# Back.net
KiCad netlist of a schematic drawn in Altium Designer
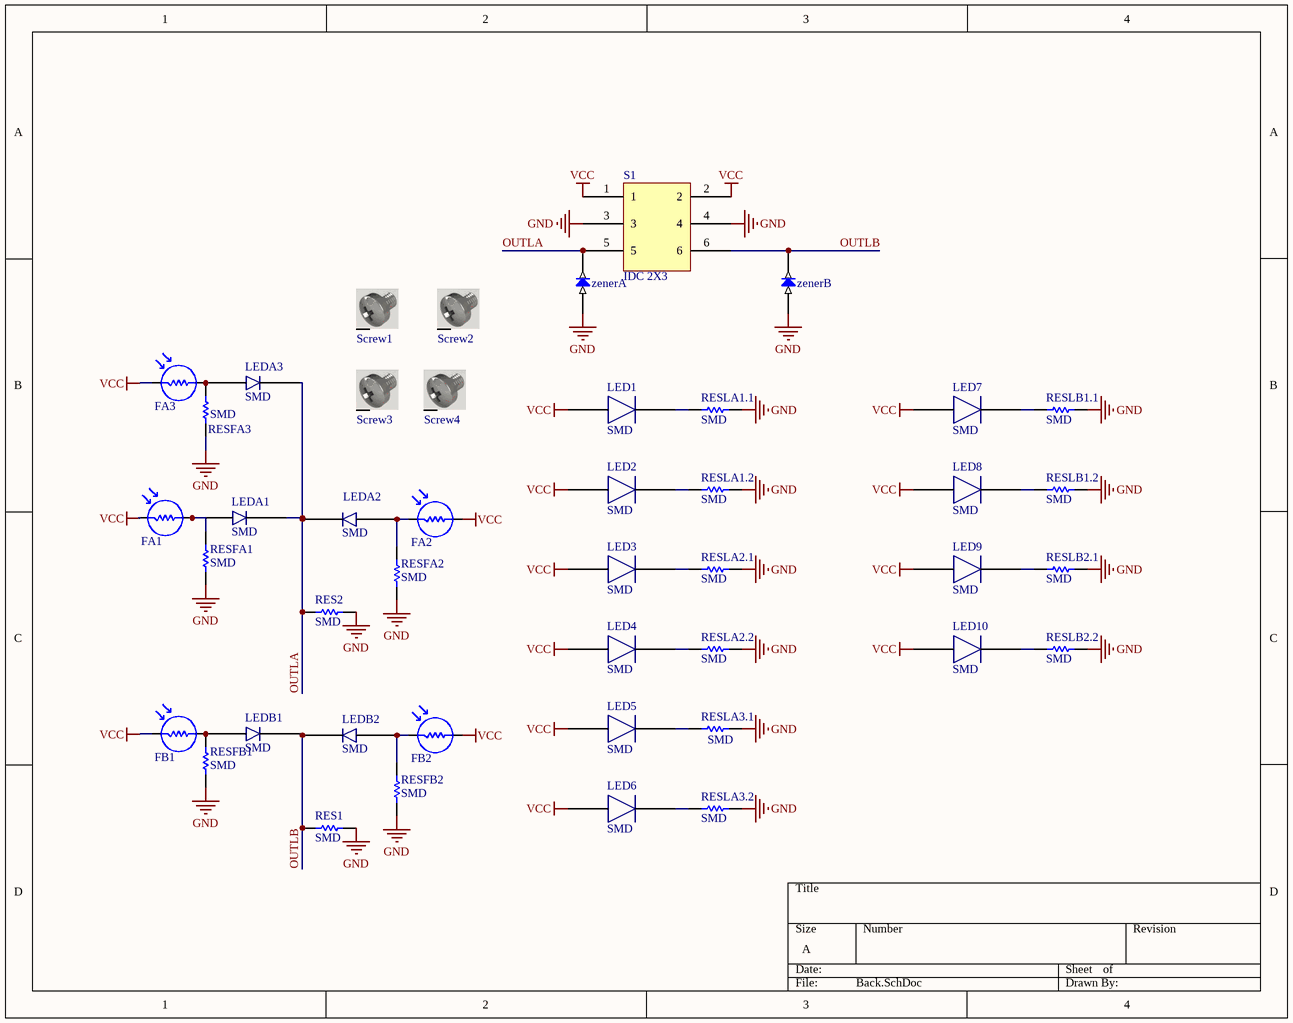
[diagram p0: Back.SchDoc]

(export (version "E")
  (design (tool "Eeschema 10.0.6"))
  (components
    (comp (ref "FA1")
      (value "Photo Cell")
      (footprint "PhotoCell.")
      (fields (field (name "PUBLISHER") "Altium Limited"))
      (libsource (lib "Farzanegan") (part "Photo Cell.."))
    )
    (comp (ref "FA2")
      (value "Photo Cell")
      (footprint "PhotoCell.")
      (fields (field (name "PUBLISHER") "Altium Limited"))
      (libsource (lib "Farzanegan") (part "Photo Cell.."))
    )
    (comp (ref "FA3")
      (value "Photo Cell")
      (footprint "PhotoCell.")
      (fields (field (name "PUBLISHER") "Altium Limited"))
      (libsource (lib "Farzanegan") (part "Photo Cell.."))
    )
    (comp (ref "FB1")
      (value "Photo Cell")
      (footprint "PhotoCell.")
      (fields (field (name "PUBLISHER") "Altium Limited"))
      (libsource (lib "Farzanegan") (part "Photo Cell.."))
    )
    (comp (ref "FB2")
      (value "Photo Cell")
      (footprint "PhotoCell.")
      (fields (field (name "PUBLISHER") "Altium Limited"))
      (libsource (lib "Farzanegan") (part "Photo Cell.."))
    )
    (comp (ref "LED1") (value "SMD") (footprint "LED SMD") (libsource (lib "Farzanegan") (part "LED SMD")))
    (comp (ref "LED2") (value "SMD") (footprint "LED SMD") (libsource (lib "Farzanegan") (part "LED SMD")))
    (comp (ref "LED3") (value "SMD") (footprint "LED SMD") (libsource (lib "Farzanegan") (part "LED SMD")))
    (comp (ref "LED4") (value "SMD") (footprint "LED SMD") (libsource (lib "Farzanegan") (part "LED SMD")))
    (comp (ref "LED5") (value "SMD") (footprint "LED SMD") (libsource (lib "Farzanegan") (part "LED SMD")))
    (comp (ref "LED6") (value "SMD") (footprint "LED SMD") (libsource (lib "Farzanegan") (part "LED SMD")))
    (comp (ref "LED7") (value "SMD") (footprint "LED SMD") (libsource (lib "Farzanegan") (part "LED SMD")))
    (comp (ref "LED8") (value "SMD") (footprint "LED SMD") (libsource (lib "Farzanegan") (part "LED SMD")))
    (comp (ref "LED9") (value "SMD") (footprint "LED SMD") (libsource (lib "Farzanegan") (part "LED SMD")))
    (comp (ref "LED10") (value "SMD") (footprint "LED SMD") (libsource (lib "Farzanegan") (part "LED SMD")))
    (comp (ref "LEDA1") (value "SMD") (footprint "LED SMD") (libsource (lib "") (part "LED SMD_1")))
    (comp (ref "LEDA2") (value "SMD") (footprint "LED SMD") (libsource (lib "") (part "LED SMD_1")))
    (comp (ref "LEDA3") (value "SMD") (footprint "LED SMD") (libsource (lib "") (part "LED SMD_1")))
    (comp (ref "LEDB1") (value "SMD") (footprint "LED SMD") (libsource (lib "") (part "LED SMD_1")))
    (comp (ref "LEDB2") (value "SMD") (footprint "LED SMD") (libsource (lib "") (part "LED SMD_1")))
    (comp (ref "RES1")
      (value "SMD")
      (footprint "Resistor SMD 1206")
      (libsource (lib "Farzanegan") (part "Res SMD"))
    )
    (comp (ref "RES2")
      (value "SMD")
      (footprint "Resistor SMD 1206")
      (libsource (lib "Farzanegan") (part "Res SMD"))
    )
    (comp (ref "RESFA1")
      (value "SMD")
      (footprint "Resistor SMD 1206")
      (libsource (lib "Farzanegan") (part "Res SMD"))
    )
    (comp (ref "RESFA2")
      (value "SMD")
      (footprint "Resistor SMD 1206")
      (libsource (lib "Farzanegan") (part "Res SMD"))
    )
    (comp (ref "RESFA3")
      (value "SMD")
      (footprint "Resistor SMD 1206")
      (libsource (lib "Farzanegan") (part "Res SMD"))
    )
    (comp (ref "RESFB1")
      (value "SMD")
      (footprint "Resistor SMD 1206")
      (libsource (lib "Farzanegan") (part "Res SMD"))
    )
    (comp (ref "RESFB2")
      (value "SMD")
      (footprint "Resistor SMD 1206")
      (libsource (lib "Farzanegan") (part "Res SMD"))
    )
    (comp (ref "RESLA1.1")
      (value "SMD")
      (footprint "Resistor SMD 1206")
      (libsource (lib "Farzanegan") (part "Res SMD"))
    )
    (comp (ref "RESLA1.2")
      (value "SMD")
      (footprint "Resistor SMD 1206")
      (libsource (lib "Farzanegan") (part "Res SMD"))
    )
    (comp (ref "RESLA2.1")
      (value "SMD")
      (footprint "Resistor SMD 1206")
      (libsource (lib "Farzanegan") (part "Res SMD"))
    )
    (comp (ref "RESLA2.2")
      (value "SMD")
      (footprint "Resistor SMD 1206")
      (libsource (lib "Farzanegan") (part "Res SMD"))
    )
    (comp (ref "RESLA3.1")
      (value "SMD")
      (footprint "Resistor SMD 1206")
      (libsource (lib "Farzanegan") (part "Res SMD"))
    )
    (comp (ref "RESLA3.2")
      (value "SMD")
      (footprint "Resistor SMD 1206")
      (libsource (lib "Farzanegan") (part "Res SMD"))
    )
    (comp (ref "RESLB1.1")
      (value "SMD")
      (footprint "Resistor SMD 1206")
      (libsource (lib "Farzanegan") (part "Res SMD"))
    )
    (comp (ref "RESLB1.2")
      (value "SMD")
      (footprint "Resistor SMD 1206")
      (libsource (lib "Farzanegan") (part "Res SMD"))
    )
    (comp (ref "RESLB2.1")
      (value "SMD")
      (footprint "Resistor SMD 1206")
      (libsource (lib "Farzanegan") (part "Res SMD"))
    )
    (comp (ref "RESLB2.2")
      (value "SMD")
      (footprint "Resistor SMD 1206")
      (libsource (lib "Farzanegan") (part "Res SMD"))
    )
    (comp (ref "S1") (value "IDC 2X3") (footprint "IDC 2X3") (libsource (lib "Farzanegan") (part "IDC 2X3")))
    (comp (ref "Screw1")
      (value "Screw")
      (footprint "Screw")
      (fields (field (name "PUBLISHER") "Altium Limited"))
      (libsource (lib "Farzanegan") (part "Screw"))
    )
    (comp (ref "Screw2")
      (value "Screw")
      (footprint "Screw")
      (fields (field (name "PUBLISHER") "Altium Limited"))
      (libsource (lib "Farzanegan") (part "Screw"))
    )
    (comp (ref "Screw3")
      (value "Screw")
      (footprint "Screw")
      (fields (field (name "PUBLISHER") "Altium Limited"))
      (libsource (lib "Farzanegan") (part "Screw"))
    )
    (comp (ref "Screw4")
      (value "Screw")
      (footprint "Screw")
      (fields (field (name "PUBLISHER") "Altium Limited"))
      (libsource (lib "Farzanegan") (part "Screw"))
    )
    (comp (ref "zenerA")
      (value "zener")
      (footprint "LED SMD")
      (libsource (lib "Farz1") (part "SMDZenerDiode"))
    )
    (comp (ref "zenerB")
      (value "zener")
      (footprint "LED SMD")
      (libsource (lib "Farz1") (part "SMDZenerDiode"))
    )
  )
  (nets
    (net (code "1") (name "/OUTLA") (class "Default")
      (node (ref "LEDA1") (pin "2") (pinfunction "2_2") (pintype "passive"))
      (node (ref "LEDA2") (pin "2") (pinfunction "2_2") (pintype "passive"))
      (node (ref "LEDA3") (pin "2") (pinfunction "2_2") (pintype "passive"))
      (node (ref "RES2") (pin "1") (pinfunction "1_1") (pintype "passive"))
      (node (ref "S1") (pin "5") (pinfunction "5_5") (pintype "passive"))
      (node (ref "zenerA") (pin "2") (pinfunction "out_2") (pintype "output"))
    )
    (net (code "2") (name "/OUTLB") (class "Default")
      (node (ref "LEDB1") (pin "2") (pinfunction "2_2") (pintype "passive"))
      (node (ref "LEDB2") (pin "2") (pinfunction "2_2") (pintype "passive"))
      (node (ref "RES1") (pin "1") (pinfunction "1_1") (pintype "passive"))
      (node (ref "S1") (pin "6") (pinfunction "6_6") (pintype "passive"))
      (node (ref "zenerB") (pin "2") (pinfunction "out_2") (pintype "output"))
    )
    (net (code "3") (name "GND") (class "Default")
      (node (ref "RES1") (pin "2") (pinfunction "2_2") (pintype "passive"))
      (node (ref "RES2") (pin "2") (pinfunction "2_2") (pintype "passive"))
      (node (ref "RESFA1") (pin "1") (pinfunction "1_1") (pintype "passive"))
      (node (ref "RESFA2") (pin "1") (pinfunction "1_1") (pintype "passive"))
      (node (ref "RESFA3") (pin "1") (pinfunction "1_1") (pintype "passive"))
      (node (ref "RESFB1") (pin "1") (pinfunction "1_1") (pintype "passive"))
      (node (ref "RESFB2") (pin "1") (pinfunction "1_1") (pintype "passive"))
      (node (ref "RESLA1.1") (pin "2") (pinfunction "2_2") (pintype "passive"))
      (node (ref "RESLA1.2") (pin "2") (pinfunction "2_2") (pintype "passive"))
      (node (ref "RESLA2.1") (pin "2") (pinfunction "2_2") (pintype "passive"))
      (node (ref "RESLA2.2") (pin "2") (pinfunction "2_2") (pintype "passive"))
      (node (ref "RESLA3.1") (pin "2") (pinfunction "2_2") (pintype "passive"))
      (node (ref "RESLA3.2") (pin "2") (pinfunction "2_2") (pintype "passive"))
      (node (ref "RESLB1.1") (pin "2") (pinfunction "2_2") (pintype "passive"))
      (node (ref "RESLB1.2") (pin "2") (pinfunction "2_2") (pintype "passive"))
      (node (ref "RESLB2.1") (pin "2") (pinfunction "2_2") (pintype "passive"))
      (node (ref "RESLB2.2") (pin "2") (pinfunction "2_2") (pintype "passive"))
      (node (ref "S1") (pin "3") (pinfunction "3_3") (pintype "passive"))
      (node (ref "S1") (pin "4") (pinfunction "4_4") (pintype "passive"))
      (node (ref "zenerA") (pin "1") (pinfunction "in_1") (pintype "input"))
      (node (ref "zenerB") (pin "1") (pinfunction "in_1") (pintype "input"))
    )
    (net (code "4") (name "Net-(FA1-Pad2)") (class "Default")
      (node (ref "FA1") (pin "2") (pintype "passive"))
      (node (ref "LEDA1") (pin "1") (pinfunction "1_1") (pintype "passive"))
      (node (ref "RESFA1") (pin "2") (pinfunction "2_2") (pintype "passive"))
    )
    (net (code "5") (name "Net-(FA2-Pad1)") (class "Default")
      (node (ref "FA2") (pin "1") (pintype "passive"))
      (node (ref "LEDA2") (pin "1") (pinfunction "1_1") (pintype "passive"))
      (node (ref "RESFA2") (pin "2") (pinfunction "2_2") (pintype "passive"))
    )
    (net (code "6") (name "Net-(FA3-Pad2)") (class "Default")
      (node (ref "FA3") (pin "2") (pintype "passive"))
      (node (ref "LEDA3") (pin "1") (pinfunction "1_1") (pintype "passive"))
      (node (ref "RESFA3") (pin "2") (pinfunction "2_2") (pintype "passive"))
    )
    (net (code "7") (name "Net-(FB1-Pad2)") (class "Default")
      (node (ref "FB1") (pin "2") (pintype "passive"))
      (node (ref "LEDB1") (pin "1") (pinfunction "1_1") (pintype "passive"))
      (node (ref "RESFB1") (pin "2") (pinfunction "2_2") (pintype "passive"))
    )
    (net (code "8") (name "Net-(FB2-Pad1)") (class "Default")
      (node (ref "FB2") (pin "1") (pintype "passive"))
      (node (ref "LEDB2") (pin "1") (pinfunction "1_1") (pintype "passive"))
      (node (ref "RESFB2") (pin "2") (pinfunction "2_2") (pintype "passive"))
    )
    (net (code "9") (name "Net-(LED1-Pad2)") (class "Default")
      (node (ref "LED1") (pin "2") (pinfunction "2_2") (pintype "passive"))
      (node (ref "RESLA1.1") (pin "1") (pinfunction "1_1") (pintype "passive"))
    )
    (net (code "10") (name "Net-(LED2-Pad2)") (class "Default")
      (node (ref "LED2") (pin "2") (pinfunction "2_2") (pintype "passive"))
      (node (ref "RESLA1.2") (pin "1") (pinfunction "1_1") (pintype "passive"))
    )
    (net (code "11") (name "Net-(LED3-Pad2)") (class "Default")
      (node (ref "LED3") (pin "2") (pinfunction "2_2") (pintype "passive"))
      (node (ref "RESLA2.1") (pin "1") (pinfunction "1_1") (pintype "passive"))
    )
    (net (code "12") (name "Net-(LED4-Pad2)") (class "Default")
      (node (ref "LED4") (pin "2") (pinfunction "2_2") (pintype "passive"))
      (node (ref "RESLA2.2") (pin "1") (pinfunction "1_1") (pintype "passive"))
    )
    (net (code "13") (name "Net-(LED5-Pad2)") (class "Default")
      (node (ref "LED5") (pin "2") (pinfunction "2_2") (pintype "passive"))
      (node (ref "RESLA3.1") (pin "1") (pinfunction "1_1") (pintype "passive"))
    )
    (net (code "14") (name "Net-(LED6-Pad2)") (class "Default")
      (node (ref "LED6") (pin "2") (pinfunction "2_2") (pintype "passive"))
      (node (ref "RESLA3.2") (pin "1") (pinfunction "1_1") (pintype "passive"))
    )
    (net (code "15") (name "Net-(LED7-Pad2)") (class "Default")
      (node (ref "LED7") (pin "2") (pinfunction "2_2") (pintype "passive"))
      (node (ref "RESLB1.1") (pin "1") (pinfunction "1_1") (pintype "passive"))
    )
    (net (code "16") (name "Net-(LED8-Pad2)") (class "Default")
      (node (ref "LED8") (pin "2") (pinfunction "2_2") (pintype "passive"))
      (node (ref "RESLB1.2") (pin "1") (pinfunction "1_1") (pintype "passive"))
    )
    (net (code "17") (name "Net-(LED9-Pad2)") (class "Default")
      (node (ref "LED9") (pin "2") (pinfunction "2_2") (pintype "passive"))
      (node (ref "RESLB2.1") (pin "1") (pinfunction "1_1") (pintype "passive"))
    )
    (net (code "18") (name "Net-(LED10-Pad2)") (class "Default")
      (node (ref "LED10") (pin "2") (pinfunction "2_2") (pintype "passive"))
      (node (ref "RESLB2.2") (pin "1") (pinfunction "1_1") (pintype "passive"))
    )
    (net (code "19") (name "VCC") (class "Default")
      (node (ref "FA1") (pin "1") (pintype "passive"))
      (node (ref "FA2") (pin "2") (pintype "passive"))
      (node (ref "FA3") (pin "1") (pintype "passive"))
      (node (ref "FB1") (pin "1") (pintype "passive"))
      (node (ref "FB2") (pin "2") (pintype "passive"))
      (node (ref "LED1") (pin "1") (pinfunction "1_1") (pintype "passive"))
      (node (ref "LED10") (pin "1") (pinfunction "1_1") (pintype "passive"))
      (node (ref "LED2") (pin "1") (pinfunction "1_1") (pintype "passive"))
      (node (ref "LED3") (pin "1") (pinfunction "1_1") (pintype "passive"))
      (node (ref "LED4") (pin "1") (pinfunction "1_1") (pintype "passive"))
      (node (ref "LED5") (pin "1") (pinfunction "1_1") (pintype "passive"))
      (node (ref "LED6") (pin "1") (pinfunction "1_1") (pintype "passive"))
      (node (ref "LED7") (pin "1") (pinfunction "1_1") (pintype "passive"))
      (node (ref "LED8") (pin "1") (pinfunction "1_1") (pintype "passive"))
      (node (ref "LED9") (pin "1") (pinfunction "1_1") (pintype "passive"))
      (node (ref "S1") (pin "1") (pinfunction "1_1") (pintype "passive"))
      (node (ref "S1") (pin "2") (pinfunction "2_2") (pintype "passive"))
    )
    (net (code "20") (name "unconnected-(Screw1-PadS)") (class "Default")
      (node (ref "Screw1") (pin "S") (pinfunction "S_S") (pintype "passive"))
    )
    (net (code "21") (name "unconnected-(Screw2-PadS)") (class "Default")
      (node (ref "Screw2") (pin "S") (pinfunction "S_S") (pintype "passive"))
    )
    (net (code "22") (name "unconnected-(Screw3-PadS)") (class "Default")
      (node (ref "Screw3") (pin "S") (pinfunction "S_S") (pintype "passive"))
    )
    (net (code "23") (name "unconnected-(Screw4-PadS)") (class "Default")
      (node (ref "Screw4") (pin "S") (pinfunction "S_S") (pintype "passive"))
    )
  )
)
